# Sheet1.net
KiCad netlist of a schematic drawn in Altium Designer
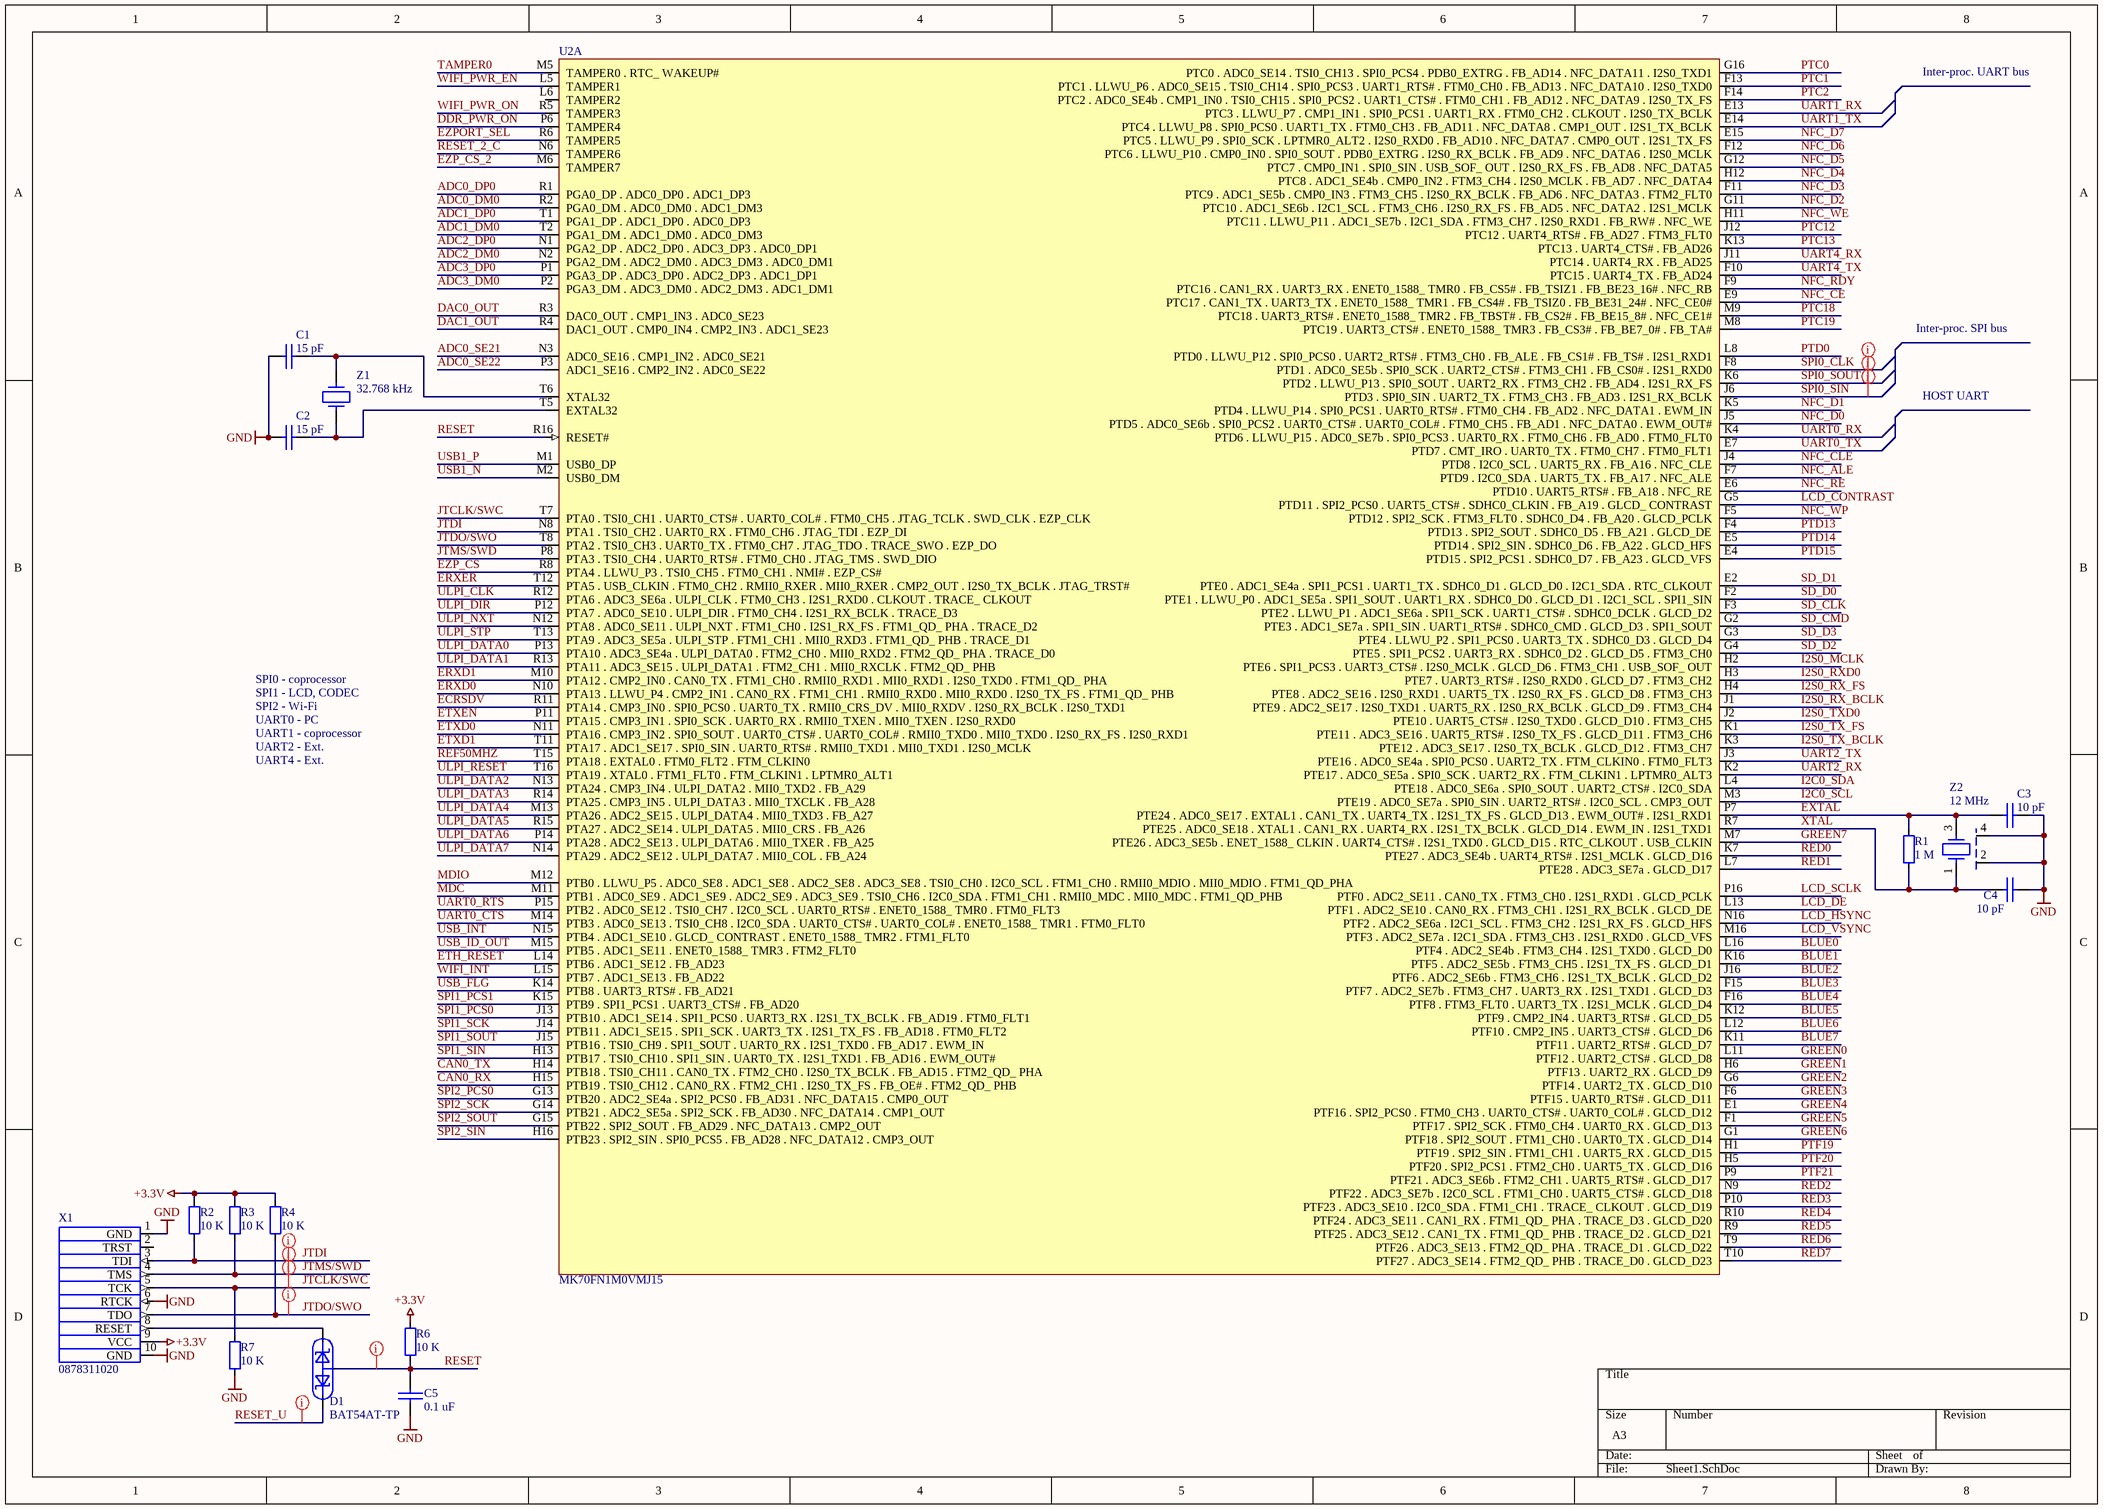
[diagram p0: Sheet1.SchDoc]

(export (version "E")
  (design (tool "Eeschema 10.0.6"))
  (components
    (comp (ref "C1")
      (value "15 pF")
      (footprint "1608[0603]")
      (description "15 pF, 50V, 5%, NP0, 0603 SMD MLC Capacitor")
      (fields (field (name "MANUFACTURER") "YAGEO AMERICA CORPORATION") (field (name "TOLERANCE") "5%"))
      (libsource (lib "ea_Capacitors") (part "CCPF015K0603"))
    )
    (comp (ref "C2")
      (value "15 pF")
      (footprint "1608[0603]")
      (description "15 pF, 50V, 5%, NP0, 0603 SMD MLC Capacitor")
      (fields (field (name "MANUFACTURER") "YAGEO AMERICA CORPORATION") (field (name "TOLERANCE") "5%"))
      (libsource (lib "ea_Capacitors") (part "CCPF015K0603"))
    )
    (comp (ref "C3")
      (value "10 pF")
      (footprint "1608[0603]")
      (description "10 pF, 50V, 5%, NP0, 0603 SMD MLC Capacitor")
      (fields (field (name "MANUFACTURER") "Kemet") (field (name "TOLERANCE") "5%"))
      (libsource (lib "ea_Capacitors") (part "CCPF010K0603"))
    )
    (comp (ref "C4")
      (value "10 pF")
      (footprint "1608[0603]")
      (description "10 pF, 50V, 5%, NP0, 0603 SMD MLC Capacitor")
      (fields (field (name "MANUFACTURER") "Kemet") (field (name "TOLERANCE") "5%"))
      (libsource (lib "ea_Capacitors") (part "CCPF010K0603"))
    )
    (comp (ref "C5")
      (value "0.1 uF")
      (footprint "1005[0402]")
      (description "0.1 uF, 16V, 10%, X7R, 0402")
      (fields (field (name "TOLERANCE") "10%") (field (name "MANUFACTURER") "Murata"))
      (libsource (lib "ea_Capacitors") (part "GRM155R71C104KA88D"))
    )
    (comp (ref "D1")
      (value "BAT54AT-TP")
      (footprint "SOT-523F")
      (description "Schottky Diode, 30 V, 200 mA, common anode, SOT523")
      (fields (field (name "MANUFACTURER") "Micro Commercial Co") (field (name "PARTNUM") "BAT54AT-TPDKR-ND"))
      (libsource (lib "ea_Diodes") (part "BAT54AT-TP"))
    )
    (comp (ref "R1")
      (value "1 M")
      (footprint "0603")
      (description "1 M, 1%, 0603, SMD Resistor, Taped")
      (fields (field (name "MANUFACTURER") "YAGEO AMERICA CORPORATION") (field (name "TOLERANCE") "1%"))
      (libsource (lib "ea_Resistors") (part "RC0603FR-071ML"))
    )
    (comp (ref "R2")
      (value "10 K")
      (footprint "0402")
      (description "10 K, 5%, 0402, SMD Resistor, Taped")
      (fields (field (name "MANUFACTURER") "Yageo") (field (name "TOLERANCE") "5%"))
      (libsource (lib "ea_Resistors") (part "RC0402JR-0710KL"))
    )
    (comp (ref "R3")
      (value "10 K")
      (footprint "0402")
      (description "10 K, 5%, 0402, SMD Resistor, Taped")
      (fields (field (name "MANUFACTURER") "Yageo") (field (name "TOLERANCE") "5%"))
      (libsource (lib "ea_Resistors") (part "RC0402JR-0710KL"))
    )
    (comp (ref "R4")
      (value "10 K")
      (footprint "0402")
      (description "10 K, 5%, 0402, SMD Resistor, Taped")
      (fields (field (name "MANUFACTURER") "Yageo") (field (name "TOLERANCE") "5%"))
      (libsource (lib "ea_Resistors") (part "RC0402JR-0710KL"))
    )
    (comp (ref "R6")
      (value "10 K")
      (footprint "0402")
      (description "10 K, 5%, 0402, SMD Resistor, Taped")
      (fields (field (name "MANUFACTURER") "Yageo") (field (name "TOLERANCE") "5%"))
      (libsource (lib "ea_Resistors") (part "RC0402JR-0710KL"))
    )
    (comp (ref "R7")
      (value "10 K")
      (footprint "0402")
      (description "10 K, 5%, 0402, SMD Resistor, Taped")
      (fields (field (name "MANUFACTURER") "Yageo") (field (name "TOLERANCE") "5%"))
      (libsource (lib "ea_Resistors") (part "RC0402JR-0710KL"))
    )
    (comp (ref "U2")
      (value "MK70FN1M0VMJ15")
      (footprint "MAPBGA 256-pin")
      (description "32-Bit 150 Mhz ARM 1MB FLASH 256MAPBGA")
      (fields (field (name "MANUFACTURER") "Freescale") (field (name "PARTNUM") "MK70FN1M0VMJ15-ND"))
      (libsource (lib "ea_IC_CPU") (part "MK70FN1M0VMJ15"))
    )
    (comp (ref "X1")
      (value "0878311020")
      (footprint "878311020 MGRID WALL HDR SMD")
      (description "JTAG, CONN HEADER 10POS 2MM VERT SMD")
      (fields (field (name "MANUFACTURER") "Molex Inc") (field (name "PARTNUM") "WM18639-ND"))
      (libsource (lib "ea_Connectors") (part "0878321020"))
    )
    (comp (ref "Z1")
      (value "32.768 kHz")
      (footprint "ABS10")
      (description "32.768 kHz, 12.5 pF, 70 kOhm, ±20ppm, -40°C ~ 80°C")
      (fields (field (name "MANUFACTURER") "Abracon Corporation") (field (name "PARTNUM") "535-9536-1-ND"))
      (libsource (lib "ea_OSC_CLK_GEN") (part "ABS10-32.768KHZ-T"))
    )
    (comp (ref "Z2")
      (value "12 MHz")
      (footprint "DSX321G")
      (description "12 MHz, 8 pF, ±15ppm, -10...+75 С")
      (fields (field (name "MANUFACTURER") "NDK") (field (name "PARTNUM") "644-1047-1-ND"))
      (libsource (lib "ea_OSC_CLK_GEN") (part "NX3225SA-12.000MHZ-STD-CSR-1"))
    )
  )
  (nets
    (net (code "1") (name "+3.3V") (class "Default")
      (node (ref "R2") (pin "1") (pinfunction "1_1") (pintype "passive"))
      (node (ref "R3") (pin "1") (pinfunction "1_1") (pintype "passive"))
      (node (ref "R4") (pin "1") (pinfunction "1_1") (pintype "passive"))
      (node (ref "R6") (pin "1") (pinfunction "1_1") (pintype "passive"))
      (node (ref "X1") (pin "9") (pinfunction "VCC_9") (pintype "power_in"))
    )
    (net (code "2") (name "/ADC0_DM0") (class "Default")
      (node (ref "U2") (pin "R2") (pinfunction "PGA0_DM_._ADC0_DM0_._ADC1_DM3_R2") (pintype "bidirectional"))
    )
    (net (code "3") (name "/ADC0_DP0") (class "Default")
      (node (ref "U2") (pin "R1") (pinfunction "PGA0_DP_._ADC0_DP0_._ADC1_DP3_R1") (pintype "bidirectional"))
    )
    (net (code "4") (name "/ADC0_SE21") (class "Default")
      (node (ref "U2") (pin "N3") (pinfunction "ADC0_SE16_._CMP1_IN2_._ADC0_SE21_N3") (pintype "bidirectional"))
    )
    (net (code "5") (name "/ADC0_SE22") (class "Default")
      (node (ref "U2") (pin "P3") (pinfunction "ADC1_SE16_._CMP2_IN2_._ADC0_SE22_P3") (pintype "bidirectional"))
    )
    (net (code "6") (name "/ADC1_DM0") (class "Default")
      (node (ref "U2") (pin "T2") (pinfunction "PGA1_DM_._ADC1_DM0_._ADC0_DM3_T2") (pintype "bidirectional"))
    )
    (net (code "7") (name "/ADC1_DP0") (class "Default")
      (node (ref "U2") (pin "T1") (pinfunction "PGA1_DP_._ADC1_DP0_._ADC0_DP3_T1") (pintype "bidirectional"))
    )
    (net (code "8") (name "/ADC2_DM0") (class "Default")
      (node (ref "U2") (pin "N2") (pinfunction "PGA2_DM_._ADC2_DM0_._ADC3_DM3_._ADC0_DM1_N2") (pintype "bidirectional"))
    )
    (net (code "9") (name "/ADC2_DP0") (class "Default")
      (node (ref "U2") (pin "N1") (pinfunction "PGA2_DP_._ADC2_DP0_._ADC3_DP3_._ADC0_DP1_N1") (pintype "bidirectional"))
    )
    (net (code "10") (name "/ADC3_DM0") (class "Default")
      (node (ref "U2") (pin "P2") (pinfunction "PGA3_DM_._ADC3_DM0_._ADC2_DM3_._ADC1_DM1_P2") (pintype "bidirectional"))
    )
    (net (code "11") (name "/ADC3_DP0") (class "Default")
      (node (ref "U2") (pin "P1") (pinfunction "PGA3_DP_._ADC3_DP0_._ADC2_DP3_._ADC1_DP1_P1") (pintype "bidirectional"))
    )
    (net (code "12") (name "/BLUE0") (class "Default")
      (node (ref "U2") (pin "L16") (pinfunction "PTF4_._ADC2_SE4b_._FTM3_CH4_._I2S1_TXD0_._GLCD_D0_L16") (pintype "bidirectional"))
    )
    (net (code "13") (name "/BLUE1") (class "Default")
      (node (ref "U2") (pin "K16") (pinfunction "PTF5_._ADC2_SE5b_._FTM3_CH5_._I2S1_TX_FS_._GLCD_D1_K16") (pintype "bidirectional"))
    )
    (net (code "14") (name "/BLUE2") (class "Default")
      (node (ref "U2") (pin "J16") (pinfunction "PTF6_._ADC2_SE6b_._FTM3_CH6_._I2S1_TX_BCLK_._GLCD_D2_J16") (pintype "bidirectional"))
    )
    (net (code "15") (name "/BLUE3") (class "Default")
      (node (ref "U2") (pin "F15") (pinfunction "PTF7_._ADC2_SE7b_._FTM3_CH7_._UART3_RX_._I2S1_TXD1_._GLCD_D3_F15") (pintype "bidirectional"))
    )
    (net (code "16") (name "/BLUE4") (class "Default")
      (node (ref "U2") (pin "F16") (pinfunction "PTF8_._FTM3_FLT0_._UART3_TX_._I2S1_MCLK_._GLCD_D4_F16") (pintype "bidirectional"))
    )
    (net (code "17") (name "/BLUE5") (class "Default")
      (node (ref "U2") (pin "K12") (pinfunction "PTF9_._CMP2_IN4_._UART3_RTS#_._GLCD_D5_K12") (pintype "bidirectional"))
    )
    (net (code "18") (name "/BLUE6") (class "Default")
      (node (ref "U2") (pin "L12") (pinfunction "PTF10_._CMP2_IN5_._UART3_CTS#_._GLCD_D6_L12") (pintype "bidirectional"))
    )
    (net (code "19") (name "/BLUE7") (class "Default")
      (node (ref "U2") (pin "K11") (pinfunction "PTF11_._UART2_RTS#_._GLCD_D7_K11") (pintype "bidirectional"))
    )
    (net (code "20") (name "/CAN0_RX") (class "Default")
      (node (ref "U2") (pin "H15") (pinfunction "PTB19_._TSI0_CH12_._CAN0_RX_._FTM2_CH1_._I2S0_TX_FS_._FB_OE#_._FTM2_QD__PHB_H15") (pintype "bidirectional"))
    )
    (net (code "21") (name "/CAN0_TX") (class "Default")
      (node (ref "U2") (pin "H14") (pinfunction "PTB18_._TSI0_CH11_._CAN0_TX_._FTM2_CH0_._I2S0_TX_BCLK_._FB_AD15_._FTM2_QD__PHA_H14") (pintype "bidirectional"))
    )
    (net (code "22") (name "/DAC0_OUT") (class "Default")
      (node (ref "U2") (pin "R3") (pinfunction "DAC0_OUT_._CMP1_IN3_._ADC0_SE23_R3") (pintype "bidirectional"))
    )
    (net (code "23") (name "/DAC1_OUT") (class "Default")
      (node (ref "U2") (pin "R4") (pinfunction "DAC1_OUT_._CMP0_IN4_._CMP2_IN3_._ADC1_SE23_R4") (pintype "bidirectional"))
    )
    (net (code "24") (name "/DDR_PWR_ON") (class "Default")
      (node (ref "U2") (pin "P6") (pinfunction "TAMPER4_P6") (pintype "bidirectional"))
    )
    (net (code "25") (name "/ECRSDV") (class "Default")
      (node (ref "U2") (pin "R11") (pinfunction "PTA14_._CMP3_IN0_._SPI0_PCS0_._UART0_TX_._RMII0_CRS_DV_._MII0_RXDV_._I2S0_RX_BCLK_._I2S0_TXD1_R11") (pintype "bidirectional"))
    )
    (net (code "26") (name "/ERXD0") (class "Default")
      (node (ref "U2") (pin "N10") (pinfunction "PTA13_._LLWU_P4_._CMP2_IN1_._CAN0_RX_._FTM1_CH1_._RMII0_RXD0_._MII0_RXD0_._I2S0_TX_FS_._FTM1_QD__PHB_N10") (pintype "bidirectional"))
    )
    (net (code "27") (name "/ERXD1") (class "Default")
      (node (ref "U2") (pin "M10") (pinfunction "PTA12_._CMP2_IN0_._CAN0_TX_._FTM1_CH0_._RMII0_RXD1_._MII0_RXD1_._I2S0_TXD0_._FTM1_QD__PHA_M10") (pintype "bidirectional"))
    )
    (net (code "28") (name "/ERXER") (class "Default")
      (node (ref "U2") (pin "T12") (pinfunction "PTA5_._USB_CLKIN_._FTM0_CH2_._RMII0_RXER_._MII0_RXER_._CMP2_OUT_._I2S0_TX_BCLK_._JTAG_TRST#_T12") (pintype "bidirectional"))
    )
    (net (code "29") (name "/ETH_RESET") (class "Default")
      (node (ref "U2") (pin "L14") (pinfunction "PTB6_._ADC1_SE12_._FB_AD23_L14") (pintype "bidirectional"))
    )
    (net (code "30") (name "/ETXD0") (class "Default")
      (node (ref "U2") (pin "N11") (pinfunction "PTA16_._CMP3_IN2_._SPI0_SOUT_._UART0_CTS#_._UART0_COL#_._RMII0_TXD0_._MII0_TXD0_._I2S0_RX_FS_._I2S0_RXD1_N11") (pintype "bidirectional"))
    )
    (net (code "31") (name "/ETXD1") (class "Default")
      (node (ref "U2") (pin "T11") (pinfunction "PTA17_._ADC1_SE17_._SPI0_SIN_._UART0_RTS#_._RMII0_TXD1_._MII0_TXD1_._I2S0_MCLK_T11") (pintype "bidirectional"))
    )
    (net (code "32") (name "/ETXEN") (class "Default")
      (node (ref "U2") (pin "P11") (pinfunction "PTA15_._CMP3_IN1_._SPI0_SCK_._UART0_RX_._RMII0_TXEN_._MII0_TXEN_._I2S0_RXD0_P11") (pintype "bidirectional"))
    )
    (net (code "33") (name "/EXTAL") (class "Default")
      (node (ref "C3") (pin "1") (pinfunction "1_1") (pintype "passive"))
      (node (ref "R1") (pin "2") (pinfunction "2_2") (pintype "passive"))
      (node (ref "U2") (pin "P7") (pinfunction "PTE24_._ADC0_SE17_._EXTAL1_._CAN1_TX_._UART4_TX_._I2S1_TX_FS_._GLCD_D13_._EWM_OUT#_._I2S1_RXD1_P7") (pintype "bidirectional"))
      (node (ref "Z2") (pin "3") (pinfunction "3_3") (pintype "passive"))
    )
    (net (code "34") (name "/EZPORT_SEL") (class "Default")
      (node (ref "U2") (pin "R6") (pinfunction "TAMPER5_R6") (pintype "bidirectional"))
    )
    (net (code "35") (name "/EZP_CS") (class "Default")
      (node (ref "U2") (pin "R8") (pinfunction "PTA4_._LLWU_P3_._TSI0_CH5_._FTM0_CH1_._NMI#_._EZP_CS#_R8") (pintype "bidirectional"))
    )
    (net (code "36") (name "/EZP_CS_2") (class "Default")
      (node (ref "U2") (pin "M6") (pinfunction "TAMPER7_M6") (pintype "bidirectional"))
    )
    (net (code "37") (name "/GREEN0") (class "Default")
      (node (ref "U2") (pin "L11") (pinfunction "PTF12_._UART2_CTS#_._GLCD_D8_L11") (pintype "bidirectional"))
    )
    (net (code "38") (name "/GREEN1") (class "Default")
      (node (ref "U2") (pin "H6") (pinfunction "PTF13_._UART2_RX_._GLCD_D9_H6") (pintype "bidirectional"))
    )
    (net (code "39") (name "/GREEN2") (class "Default")
      (node (ref "U2") (pin "G6") (pinfunction "PTF14_._UART2_TX_._GLCD_D10_G6") (pintype "bidirectional"))
    )
    (net (code "40") (name "/GREEN3") (class "Default")
      (node (ref "U2") (pin "F6") (pinfunction "PTF15_._UART0_RTS#_._GLCD_D11_F6") (pintype "bidirectional"))
    )
    (net (code "41") (name "/GREEN4") (class "Default")
      (node (ref "U2") (pin "E1") (pinfunction "PTF16_._SPI2_PCS0_._FTM0_CH3_._UART0_CTS#_._UART0_COL#_._GLCD_D12_E1") (pintype "bidirectional"))
    )
    (net (code "42") (name "/GREEN5") (class "Default")
      (node (ref "U2") (pin "F1") (pinfunction "PTF17_._SPI2_SCK_._FTM0_CH4_._UART0_RX_._GLCD_D13_F1") (pintype "bidirectional"))
    )
    (net (code "43") (name "/GREEN6") (class "Default")
      (node (ref "U2") (pin "G1") (pinfunction "PTF18_._SPI2_SOUT_._FTM1_CH0_._UART0_TX_._GLCD_D14_G1") (pintype "bidirectional"))
    )
    (net (code "44") (name "/GREEN7") (class "Default")
      (node (ref "U2") (pin "M7") (pinfunction "PTE26_._ADC3_SE5b_._ENET_1588__CLKIN_._UART4_CTS#_._I2S1_TXD0_._GLCD_D15_._RTC_CLKOUT_._USB_CLKIN_M7") (pintype "bidirectional"))
    )
    (net (code "45") (name "/I2C0_SCL") (class "Default")
      (node (ref "U2") (pin "M3") (pinfunction "PTE19_._ADC0_SE7a_._SPI0_SIN_._UART2_RTS#_._I2C0_SCL_._CMP3_OUT_M3") (pintype "bidirectional"))
    )
    (net (code "46") (name "/I2C0_SDA") (class "Default")
      (node (ref "U2") (pin "L4") (pinfunction "PTE18_._ADC0_SE6a_._SPI0_SOUT_._UART2_CTS#_._I2C0_SDA_L4") (pintype "bidirectional"))
    )
    (net (code "47") (name "/I2S0_MCLK") (class "Default")
      (node (ref "U2") (pin "H2") (pinfunction "PTE6_._SPI1_PCS3_._UART3_CTS#_._I2S0_MCLK_._GLCD_D6_._FTM3_CH1_._USB_SOF__OUT_H2") (pintype "bidirectional"))
    )
    (net (code "48") (name "/I2S0_RXD0") (class "Default")
      (node (ref "U2") (pin "H3") (pinfunction "PTE7_._UART3_RTS#_._I2S0_RXD0_._GLCD_D7_._FTM3_CH2_H3") (pintype "bidirectional"))
    )
    (net (code "49") (name "/I2S0_RX_BCLK") (class "Default")
      (node (ref "U2") (pin "J1") (pinfunction "PTE9_._ADC2_SE17_._I2S0_TXD1_._UART5_RX_._I2S0_RX_BCLK_._GLCD_D9_._FTM3_CH4_J1") (pintype "bidirectional"))
    )
    (net (code "50") (name "/I2S0_RX_FS") (class "Default")
      (node (ref "U2") (pin "H4") (pinfunction "PTE8_._ADC2_SE16_._I2S0_RXD1_._UART5_TX_._I2S0_RX_FS_._GLCD_D8_._FTM3_CH3_H4") (pintype "bidirectional"))
    )
    (net (code "51") (name "/I2S0_TXD0") (class "Default")
      (node (ref "U2") (pin "J2") (pinfunction "PTE10_._UART5_CTS#_._I2S0_TXD0_._GLCD_D10_._FTM3_CH5_J2") (pintype "bidirectional"))
    )
    (net (code "52") (name "/I2S0_TX_BCLK") (class "Default")
      (node (ref "U2") (pin "K3") (pinfunction "PTE12_._ADC3_SE17_._I2S0_TX_BCLK_._GLCD_D12_._FTM3_CH7_K3") (pintype "bidirectional"))
    )
    (net (code "53") (name "/I2S0_TX_FS") (class "Default")
      (node (ref "U2") (pin "K1") (pinfunction "PTE11_._ADC3_SE16_._UART5_RTS#_._I2S0_TX_FS_._GLCD_D11_._FTM3_CH6_K1") (pintype "bidirectional"))
    )
    (net (code "54") (name "/JTCLK{slash}SWC") (class "Default")
      (node (ref "R7") (pin "1") (pinfunction "1_1") (pintype "passive"))
      (node (ref "U2") (pin "T7") (pinfunction "PTA0_._TSI0_CH1_._UART0_CTS#_._UART0_COL#_._FTM0_CH5_._JTAG_TCLK_._SWD_CLK_._EZP_CLK_T7") (pintype "bidirectional"))
      (node (ref "X1") (pin "5") (pinfunction "TCK_5") (pintype "output"))
    )
    (net (code "55") (name "/JTDI") (class "Default")
      (node (ref "R2") (pin "2") (pinfunction "2_2") (pintype "passive"))
      (node (ref "U2") (pin "N8") (pinfunction "PTA1_._TSI0_CH2_._UART0_RX_._FTM0_CH6_._JTAG_TDI_._EZP_DI_N8") (pintype "bidirectional"))
      (node (ref "X1") (pin "3") (pinfunction "TDI_3") (pintype "input"))
    )
    (net (code "56") (name "/JTDO{slash}SWO") (class "Default")
      (node (ref "R4") (pin "2") (pinfunction "2_2") (pintype "passive"))
      (node (ref "U2") (pin "T8") (pinfunction "PTA2_._TSI0_CH3_._UART0_TX_._FTM0_CH7_._JTAG_TDO_._TRACE_SWO_._EZP_DO_T8") (pintype "bidirectional"))
      (node (ref "X1") (pin "7") (pinfunction "TDO_7") (pintype "output"))
    )
    (net (code "57") (name "/JTMS{slash}SWD") (class "Default")
      (node (ref "R3") (pin "2") (pinfunction "2_2") (pintype "passive"))
      (node (ref "U2") (pin "P8") (pinfunction "PTA3_._TSI0_CH4_._UART0_RTS#_._FTM0_CH0_._JTAG_TMS_._SWD_DIO_P8") (pintype "bidirectional"))
      (node (ref "X1") (pin "4") (pinfunction "TMS_4") (pintype "output"))
    )
    (net (code "58") (name "/LCD_CONTRAST") (class "Default")
      (node (ref "U2") (pin "G5") (pinfunction "PTD11_._SPI2_PCS0_._UART5_CTS#_._SDHC0_CLKIN_._FB_A19_._GLCD__CONTRAST_G5") (pintype "bidirectional"))
    )
    (net (code "59") (name "/LCD_DE") (class "Default")
      (node (ref "U2") (pin "L13") (pinfunction "PTF1_._ADC2_SE10_._CAN0_RX_._FTM3_CH1_._I2S1_RX_BCLK_._GLCD_DE_L13") (pintype "bidirectional"))
    )
    (net (code "60") (name "/LCD_HSYNC") (class "Default")
      (node (ref "U2") (pin "N16") (pinfunction "PTF2_._ADC2_SE6a_._I2C1_SCL_._FTM3_CH2_._I2S1_RX_FS_._GLCD_HFS_N16") (pintype "bidirectional"))
    )
    (net (code "61") (name "/LCD_SCLK") (class "Default")
      (node (ref "U2") (pin "P16") (pinfunction "PTF0_._ADC2_SE11_._CAN0_TX_._FTM3_CH0_._I2S1_RXD1_._GLCD_PCLK_P16") (pintype "bidirectional"))
    )
    (net (code "62") (name "/LCD_VSYNC") (class "Default")
      (node (ref "U2") (pin "M16") (pinfunction "PTF3_._ADC2_SE7a_._I2C1_SDA_._FTM3_CH3_._I2S1_RXD0_._GLCD_VFS_M16") (pintype "bidirectional"))
    )
    (net (code "63") (name "/MDC") (class "Default")
      (node (ref "U2") (pin "M11") (pinfunction "PTB1_._ADC0_SE9_._ADC1_SE9_._ADC2_SE9_._ADC3_SE9_._TSI0_CH6_._I2C0_SDA_._FTM1_CH1_._RMII0_MDC_._MII0_MDC_._FTM1_QD_PHB_M11") (pintype "bidirectional"))
    )
    (net (code "64") (name "/MDIO") (class "Default")
      (node (ref "U2") (pin "M12") (pinfunction "PTB0_._LLWU_P5_._ADC0_SE8_._ADC1_SE8_._ADC2_SE8_._ADC3_SE8_._TSI0_CH0_._I2C0_SCL_._FTM1_CH0_._RMII0_MDIO_._MII0_MDIO_._FTM1_QD_PHA_M12") (pintype "bidirectional"))
    )
    (net (code "65") (name "/NFC_ALE") (class "Default")
      (node (ref "U2") (pin "F7") (pinfunction "PTD9_._I2C0_SDA_._UART5_TX_._FB_A17_._NFC_ALE_F7") (pintype "bidirectional"))
    )
    (net (code "66") (name "/NFC_CE") (class "Default")
      (node (ref "U2") (pin "E9") (pinfunction "PTC17_._CAN1_TX_._UART3_TX_._ENET0_1588__TMR1_._FB_CS4#_._FB_TSIZ0_._FB_BE31_24#_._NFC_CE0#_E9") (pintype "bidirectional"))
    )
    (net (code "67") (name "/NFC_CLE") (class "Default")
      (node (ref "U2") (pin "J4") (pinfunction "PTD8_._I2C0_SCL_._UART5_RX_._FB_A16_._NFC_CLE_J4") (pintype "bidirectional"))
    )
    (net (code "68") (name "/NFC_D0") (class "Default")
      (node (ref "U2") (pin "J5") (pinfunction "PTD5_._ADC0_SE6b_._SPI0_PCS2_._UART0_CTS#_._UART0_COL#_._FTM0_CH5_._FB_AD1_._NFC_DATA0_._EWM_OUT#_J5") (pintype "bidirectional"))
    )
    (net (code "69") (name "/NFC_D1") (class "Default")
      (node (ref "U2") (pin "K5") (pinfunction "PTD4_._LLWU_P14_._SPI0_PCS1_._UART0_RTS#_._FTM0_CH4_._FB_AD2_._NFC_DATA1_._EWM_IN_K5") (pintype "bidirectional"))
    )
    (net (code "70") (name "/NFC_D2") (class "Default")
      (node (ref "U2") (pin "G11") (pinfunction "PTC10_._ADC1_SE6b_._I2C1_SCL_._FTM3_CH6_._I2S0_RX_FS_._FB_AD5_._NFC_DATA2_._I2S1_MCLK_G11") (pintype "bidirectional"))
    )
    (net (code "71") (name "/NFC_D3") (class "Default")
      (node (ref "U2") (pin "F11") (pinfunction "PTC9_._ADC1_SE5b_._CMP0_IN3_._FTM3_CH5_._I2S0_RX_BCLK_._FB_AD6_._NFC_DATA3_._FTM2_FLT0_F11") (pintype "bidirectional"))
    )
    (net (code "72") (name "/NFC_D4") (class "Default")
      (node (ref "U2") (pin "H12") (pinfunction "PTC8_._ADC1_SE4b_._CMP0_IN2_._FTM3_CH4_._I2S0_MCLK_._FB_AD7_._NFC_DATA4_H12") (pintype "bidirectional"))
    )
    (net (code "73") (name "/NFC_D5") (class "Default")
      (node (ref "U2") (pin "G12") (pinfunction "PTC7_._CMP0_IN1_._SPI0_SIN_._USB_SOF__OUT_._I2S0_RX_FS_._FB_AD8_._NFC_DATA5_G12") (pintype "bidirectional"))
    )
    (net (code "74") (name "/NFC_D6") (class "Default")
      (node (ref "U2") (pin "F12") (pinfunction "PTC6_._LLWU_P10_._CMP0_IN0_._SPI0_SOUT_._PDB0_EXTRG_._I2S0_RX_BCLK_._FB_AD9_._NFC_DATA6_._I2S0_MCLK_F12") (pintype "bidirectional"))
    )
    (net (code "75") (name "/NFC_D7") (class "Default")
      (node (ref "U2") (pin "E15") (pinfunction "PTC5_._LLWU_P9_._SPI0_SCK_._LPTMR0_ALT2_._I2S0_RXD0_._FB_AD10_._NFC_DATA7_._CMP0_OUT_._I2S1_TX_FS_E15") (pintype "bidirectional"))
    )
    (net (code "76") (name "/NFC_RDY") (class "Default")
      (node (ref "U2") (pin "F9") (pinfunction "PTC16_._CAN1_RX_._UART3_RX_._ENET0_1588__TMR0_._FB_CS5#_._FB_TSIZ1_._FB_BE23_16#_._NFC_RB_F9") (pintype "bidirectional"))
    )
    (net (code "77") (name "/NFC_RE") (class "Default")
      (node (ref "U2") (pin "E6") (pinfunction "PTD10_._UART5_RTS#_._FB_A18_._NFC_RE_E6") (pintype "bidirectional"))
    )
    (net (code "78") (name "/NFC_WE") (class "Default")
      (node (ref "U2") (pin "H11") (pinfunction "PTC11_._LLWU_P11_._ADC1_SE7b_._I2C1_SDA_._FTM3_CH7_._I2S0_RXD1_._FB_RW#_._NFC_WE_H11") (pintype "bidirectional"))
    )
    (net (code "79") (name "/NFC_WP") (class "Default")
      (node (ref "U2") (pin "F5") (pinfunction "PTD12_._SPI2_SCK_._FTM3_FLT0_._SDHC0_D4_._FB_A20_._GLCD_PCLK_F5") (pintype "bidirectional"))
    )
    (net (code "80") (name "/PTC0") (class "Default")
      (node (ref "U2") (pin "G16") (pinfunction "PTC0_._ADC0_SE14_._TSI0_CH13_._SPI0_PCS4_._PDB0_EXTRG_._FB_AD14_._NFC_DATA11_._I2S0_TXD1_G16") (pintype "bidirectional"))
    )
    (net (code "81") (name "/PTC1") (class "Default")
      (node (ref "U2") (pin "F13") (pinfunction "PTC1_._LLWU_P6_._ADC0_SE15_._TSI0_CH14_._SPI0_PCS3_._UART1_RTS#_._FTM0_CH0_._FB_AD13_._NFC_DATA10_._I2S0_TXD0_F13") (pintype "bidirectional"))
    )
    (net (code "82") (name "/PTC2") (class "Default")
      (node (ref "U2") (pin "F14") (pinfunction "PTC2_._ADC0_SE4b_._CMP1_IN0_._TSI0_CH15_._SPI0_PCS2_._UART1_CTS#_._FTM0_CH1_._FB_AD12_._NFC_DATA9_._I2S0_TX_FS_F14") (pintype "bidirectional"))
    )
    (net (code "83") (name "/PTC12") (class "Default")
      (node (ref "U2") (pin "J12") (pinfunction "PTC12_._UART4_RTS#_._FB_AD27_._FTM3_FLT0_J12") (pintype "bidirectional"))
    )
    (net (code "84") (name "/PTC13") (class "Default")
      (node (ref "U2") (pin "K13") (pinfunction "PTC13_._UART4_CTS#_._FB_AD26_K13") (pintype "bidirectional"))
    )
    (net (code "85") (name "/PTC18") (class "Default")
      (node (ref "U2") (pin "M9") (pinfunction "PTC18_._UART3_RTS#_._ENET0_1588__TMR2_._FB_TBST#_._FB_CS2#_._FB_BE15_8#_._NFC_CE1#_M9") (pintype "bidirectional"))
    )
    (net (code "86") (name "/PTC19") (class "Default")
      (node (ref "U2") (pin "M8") (pinfunction "PTC19_._UART3_CTS#_._ENET0_1588__TMR3_._FB_CS3#_._FB_BE7_0#_._FB_TA#_M8") (pintype "bidirectional"))
    )
    (net (code "87") (name "/PTD0") (class "Default")
      (node (ref "U2") (pin "L8") (pinfunction "PTD0_._LLWU_P12_._SPI0_PCS0_._UART2_RTS#_._FTM3_CH0_._FB_ALE_._FB_CS1#_._FB_TS#_._I2S1_RXD1_L8") (pintype "bidirectional"))
    )
    (net (code "88") (name "/PTD13") (class "Default")
      (node (ref "U2") (pin "F4") (pinfunction "PTD13_._SPI2_SOUT_._SDHC0_D5_._FB_A21_._GLCD_DE_F4") (pintype "bidirectional"))
    )
    (net (code "89") (name "/PTD14") (class "Default")
      (node (ref "U2") (pin "E5") (pinfunction "PTD14_._SPI2_SIN_._SDHC0_D6_._FB_A22_._GLCD_HFS_E5") (pintype "bidirectional"))
    )
    (net (code "90") (name "/PTD15") (class "Default")
      (node (ref "U2") (pin "E4") (pinfunction "PTD15_._SPI2_PCS1_._SDHC0_D7_._FB_A23_._GLCD_VFS_E4") (pintype "bidirectional"))
    )
    (net (code "91") (name "/PTF19") (class "Default")
      (node (ref "U2") (pin "H1") (pinfunction "PTF19_._SPI2_SIN_._FTM1_CH1_._UART5_RX_._GLCD_D15_H1") (pintype "bidirectional"))
    )
    (net (code "92") (name "/PTF20") (class "Default")
      (node (ref "U2") (pin "H5") (pinfunction "PTF20_._SPI2_PCS1_._FTM2_CH0_._UART5_TX_._GLCD_D16_H5") (pintype "bidirectional"))
    )
    (net (code "93") (name "/PTF21") (class "Default")
      (node (ref "U2") (pin "P9") (pinfunction "PTF21_._ADC3_SE6b_._FTM2_CH1_._UART5_RTS#_._GLCD_D17_P9") (pintype "bidirectional"))
    )
    (net (code "94") (name "/RED0") (class "Default")
      (node (ref "U2") (pin "K7") (pinfunction "PTE27_._ADC3_SE4b_._UART4_RTS#_._I2S1_MCLK_._GLCD_D16_K7") (pintype "bidirectional"))
    )
    (net (code "95") (name "/RED1") (class "Default")
      (node (ref "U2") (pin "L7") (pinfunction "PTE28_._ADC3_SE7a_._GLCD_D17_L7") (pintype "bidirectional"))
    )
    (net (code "96") (name "/RED2") (class "Default")
      (node (ref "U2") (pin "N9") (pinfunction "PTF22_._ADC3_SE7b_._I2C0_SCL_._FTM1_CH0_._UART5_CTS#_._GLCD_D18_N9") (pintype "bidirectional"))
    )
    (net (code "97") (name "/RED3") (class "Default")
      (node (ref "U2") (pin "P10") (pinfunction "PTF23_._ADC3_SE10_._I2C0_SDA_._FTM1_CH1_._TRACE__CLKOUT_._GLCD_D19_P10") (pintype "bidirectional"))
    )
    (net (code "98") (name "/RED4") (class "Default")
      (node (ref "U2") (pin "R10") (pinfunction "PTF24_._ADC3_SE11_._CAN1_RX_._FTM1_QD__PHA_._TRACE_D3_._GLCD_D20_R10") (pintype "bidirectional"))
    )
    (net (code "99") (name "/RED5") (class "Default")
      (node (ref "U2") (pin "R9") (pinfunction "PTF25_._ADC3_SE12_._CAN1_TX_._FTM1_QD__PHB_._TRACE_D2_._GLCD_D21_R9") (pintype "bidirectional"))
    )
    (net (code "100") (name "/RED6") (class "Default")
      (node (ref "U2") (pin "T9") (pinfunction "PTF26_._ADC3_SE13_._FTM2_QD__PHA_._TRACE_D1_._GLCD_D22_T9") (pintype "bidirectional"))
    )
    (net (code "101") (name "/RED7") (class "Default")
      (node (ref "U2") (pin "T10") (pinfunction "PTF27_._ADC3_SE14_._FTM2_QD__PHB_._TRACE_D0_._GLCD_D23_T10") (pintype "bidirectional"))
    )
    (net (code "102") (name "/REF50MHZ") (class "Default")
      (node (ref "U2") (pin "T15") (pinfunction "PTA18_._EXTAL0_._FTM0_FLT2_._FTM_CLKIN0_T15") (pintype "bidirectional"))
    )
    (net (code "103") (name "/RESET") (class "Default")
      (node (ref "C5") (pin "1") (pinfunction "1_1") (pintype "passive"))
      (node (ref "D1") (pin "3") (pintype "passive"))
      (node (ref "R6") (pin "2") (pinfunction "2_2") (pintype "passive"))
      (node (ref "U2") (pin "R16") (pinfunction "RESET#_R16") (pintype "input"))
    )
    (net (code "104") (name "/RESET_2_C") (class "Default")
      (node (ref "U2") (pin "N6") (pinfunction "TAMPER6_N6") (pintype "bidirectional"))
    )
    (net (code "105") (name "/RESET_U") (class "Default") (node (ref "D1") (pin "2") (pintype "passive")))
    (net (code "106") (name "/SD_CLK") (class "Default")
      (node (ref "U2") (pin "F3") (pinfunction "PTE2_._LLWU_P1_._ADC1_SE6a_._SPI1_SCK_._UART1_CTS#_._SDHC0_DCLK_._GLCD_D2_F3") (pintype "bidirectional"))
    )
    (net (code "107") (name "/SD_CMD") (class "Default")
      (node (ref "U2") (pin "G2") (pinfunction "PTE3_._ADC1_SE7a_._SPI1_SIN_._UART1_RTS#_._SDHC0_CMD_._GLCD_D3_._SPI1_SOUT_G2") (pintype "bidirectional"))
    )
    (net (code "108") (name "/SD_D0") (class "Default")
      (node (ref "U2") (pin "F2") (pinfunction "PTE1_._LLWU_P0_._ADC1_SE5a_._SPI1_SOUT_._UART1_RX_._SDHC0_D0_._GLCD_D1_._I2C1_SCL_._SPI1_SIN_F2") (pintype "bidirectional"))
    )
    (net (code "109") (name "/SD_D1") (class "Default")
      (node (ref "U2") (pin "E2") (pinfunction "PTE0_._ADC1_SE4a_._SPI1_PCS1_._UART1_TX_._SDHC0_D1_._GLCD_D0_._I2C1_SDA_._RTC_CLKOUT_E2") (pintype "bidirectional"))
    )
    (net (code "110") (name "/SD_D2") (class "Default")
      (node (ref "U2") (pin "G4") (pinfunction "PTE5_._SPI1_PCS2_._UART3_RX_._SDHC0_D2_._GLCD_D5_._FTM3_CH0_G4") (pintype "bidirectional"))
    )
    (net (code "111") (name "/SD_D3") (class "Default")
      (node (ref "U2") (pin "G3") (pinfunction "PTE4_._LLWU_P2_._SPI1_PCS0_._UART3_TX_._SDHC0_D3_._GLCD_D4_G3") (pintype "bidirectional"))
    )
    (net (code "112") (name "/SPI0_CLK") (class "Default")
      (node (ref "U2") (pin "F8") (pinfunction "PTD1_._ADC0_SE5b_._SPI0_SCK_._UART2_CTS#_._FTM3_CH1_._FB_CS0#_._I2S1_RXD0_F8") (pintype "bidirectional"))
    )
    (net (code "113") (name "/SPI0_SIN") (class "Default")
      (node (ref "U2") (pin "J6") (pinfunction "PTD3_._SPI0_SIN_._UART2_TX_._FTM3_CH3_._FB_AD3_._I2S1_RX_BCLK_J6") (pintype "bidirectional"))
    )
    (net (code "114") (name "/SPI0_SOUT") (class "Default")
      (node (ref "U2") (pin "K6") (pinfunction "PTD2_._LLWU_P13_._SPI0_SOUT_._UART2_RX_._FTM3_CH2_._FB_AD4_._I2S1_RX_FS_K6") (pintype "bidirectional"))
    )
    (net (code "115") (name "/SPI1_PCS0") (class "Default")
      (node (ref "U2") (pin "J13") (pinfunction "PTB10_._ADC1_SE14_._SPI1_PCS0_._UART3_RX_._I2S1_TX_BCLK_._FB_AD19_._FTM0_FLT1_J13") (pintype "bidirectional"))
    )
    (net (code "116") (name "/SPI1_PCS1") (class "Default")
      (node (ref "U2") (pin "K15") (pinfunction "PTB9_._SPI1_PCS1_._UART3_CTS#_._FB_AD20_K15") (pintype "bidirectional"))
    )
    (net (code "117") (name "/SPI1_SCK") (class "Default")
      (node (ref "U2") (pin "J14") (pinfunction "PTB11_._ADC1_SE15_._SPI1_SCK_._UART3_TX_._I2S1_TX_FS_._FB_AD18_._FTM0_FLT2_J14") (pintype "bidirectional"))
    )
    (net (code "118") (name "/SPI1_SIN") (class "Default")
      (node (ref "U2") (pin "H13") (pinfunction "PTB17_._TSI0_CH10_._SPI1_SIN_._UART0_TX_._I2S1_TXD1_._FB_AD16_._EWM_OUT#_H13") (pintype "bidirectional"))
    )
    (net (code "119") (name "/SPI1_SOUT") (class "Default")
      (node (ref "U2") (pin "J15") (pinfunction "PTB16_._TSI0_CH9_._SPI1_SOUT_._UART0_RX_._I2S1_TXD0_._FB_AD17_._EWM_IN_J15") (pintype "bidirectional"))
    )
    (net (code "120") (name "/SPI2_PCS0") (class "Default")
      (node (ref "U2") (pin "G13") (pinfunction "PTB20_._ADC2_SE4a_._SPI2_PCS0_._FB_AD31_._NFC_DATA15_._CMP0_OUT_G13") (pintype "bidirectional"))
    )
    (net (code "121") (name "/SPI2_SCK") (class "Default")
      (node (ref "U2") (pin "G14") (pinfunction "PTB21_._ADC2_SE5a_._SPI2_SCK_._FB_AD30_._NFC_DATA14_._CMP1_OUT_G14") (pintype "bidirectional"))
    )
    (net (code "122") (name "/SPI2_SIN") (class "Default")
      (node (ref "U2") (pin "H16") (pinfunction "PTB23_._SPI2_SIN_._SPI0_PCS5_._FB_AD28_._NFC_DATA12_._CMP3_OUT_H16") (pintype "bidirectional"))
    )
    (net (code "123") (name "/SPI2_SOUT") (class "Default")
      (node (ref "U2") (pin "G15") (pinfunction "PTB22_._SPI2_SOUT_._FB_AD29_._NFC_DATA13_._CMP2_OUT_G15") (pintype "bidirectional"))
    )
    (net (code "124") (name "/TAMPER0") (class "Default")
      (node (ref "U2") (pin "M5") (pinfunction "TAMPER0_._RTC__WAKEUP#_M5") (pintype "bidirectional"))
    )
    (net (code "125") (name "/UART0_CTS") (class "Default")
      (node (ref "U2") (pin "M14") (pinfunction "PTB3_._ADC0_SE13_._TSI0_CH8_._I2C0_SDA_._UART0_CTS#_._UART0_COL#_._ENET0_1588__TMR1_._FTM0_FLT0_M14") (pintype "bidirectional"))
    )
    (net (code "126") (name "/UART0_RTS") (class "Default")
      (node (ref "U2") (pin "P15") (pinfunction "PTB2_._ADC0_SE12_._TSI0_CH7_._I2C0_SCL_._UART0_RTS#_._ENET0_1588__TMR0_._FTM0_FLT3_P15") (pintype "bidirectional"))
    )
    (net (code "127") (name "/UART0_RX") (class "Default")
      (node (ref "U2") (pin "K4") (pinfunction "PTD6_._LLWU_P15_._ADC0_SE7b_._SPI0_PCS3_._UART0_RX_._FTM0_CH6_._FB_AD0_._FTM0_FLT0_K4") (pintype "bidirectional"))
    )
    (net (code "128") (name "/UART0_TX") (class "Default")
      (node (ref "U2") (pin "E7") (pinfunction "PTD7_._CMT_IRO_._UART0_TX_._FTM0_CH7_._FTM0_FLT1_E7") (pintype "bidirectional"))
    )
    (net (code "129") (name "/UART1_RX") (class "Default")
      (node (ref "U2") (pin "E13") (pinfunction "PTC3_._LLWU_P7_._CMP1_IN1_._SPI0_PCS1_._UART1_RX_._FTM0_CH2_._CLKOUT_._I2S0_TX_BCLK_E13") (pintype "bidirectional"))
    )
    (net (code "130") (name "/UART1_TX") (class "Default")
      (node (ref "U2") (pin "E14") (pinfunction "PTC4_._LLWU_P8_._SPI0_PCS0_._UART1_TX_._FTM0_CH3_._FB_AD11_._NFC_DATA8_._CMP1_OUT_._I2S1_TX_BCLK_E14") (pintype "bidirectional"))
    )
    (net (code "131") (name "/UART2_RX") (class "Default")
      (node (ref "U2") (pin "K2") (pinfunction "PTE17_._ADC0_SE5a_._SPI0_SCK_._UART2_RX_._FTM_CLKIN1_._LPTMR0_ALT3_K2") (pintype "bidirectional"))
    )
    (net (code "132") (name "/UART2_TX") (class "Default")
      (node (ref "U2") (pin "J3") (pinfunction "PTE16_._ADC0_SE4a_._SPI0_PCS0_._UART2_TX_._FTM_CLKIN0_._FTM0_FLT3_J3") (pintype "bidirectional"))
    )
    (net (code "133") (name "/UART4_RX") (class "Default")
      (node (ref "U2") (pin "J11") (pinfunction "PTC14_._UART4_RX_._FB_AD25_J11") (pintype "bidirectional"))
    )
    (net (code "134") (name "/UART4_TX") (class "Default")
      (node (ref "U2") (pin "F10") (pinfunction "PTC15_._UART4_TX_._FB_AD24_F10") (pintype "bidirectional"))
    )
    (net (code "135") (name "/ULPI_CLK") (class "Default")
      (node (ref "U2") (pin "R12") (pinfunction "PTA6_._ADC3_SE6a_._ULPI_CLK_._FTM0_CH3_._I2S1_RXD0_._CLKOUT_._TRACE__CLKOUT_R12") (pintype "bidirectional"))
    )
    (net (code "136") (name "/ULPI_DATA0") (class "Default")
      (node (ref "U2") (pin "P13") (pinfunction "PTA10_._ADC3_SE4a_._ULPI_DATA0_._FTM2_CH0_._MII0_RXD2_._FTM2_QD__PHA_._TRACE_D0_P13") (pintype "bidirectional"))
    )
    (net (code "137") (name "/ULPI_DATA1") (class "Default")
      (node (ref "U2") (pin "R13") (pinfunction "PTA11_._ADC3_SE15_._ULPI_DATA1_._FTM2_CH1_._MII0_RXCLK_._FTM2_QD__PHB_R13") (pintype "bidirectional"))
    )
    (net (code "138") (name "/ULPI_DATA2") (class "Default")
      (node (ref "U2") (pin "N13") (pinfunction "PTA24_._CMP3_IN4_._ULPI_DATA2_._MII0_TXD2_._FB_A29_N13") (pintype "bidirectional"))
    )
    (net (code "139") (name "/ULPI_DATA3") (class "Default")
      (node (ref "U2") (pin "R14") (pinfunction "PTA25_._CMP3_IN5_._ULPI_DATA3_._MII0_TXCLK_._FB_A28_R14") (pintype "bidirectional"))
    )
    (net (code "140") (name "/ULPI_DATA4") (class "Default")
      (node (ref "U2") (pin "M13") (pinfunction "PTA26_._ADC2_SE15_._ULPI_DATA4_._MII0_TXD3_._FB_A27_M13") (pintype "bidirectional"))
    )
    (net (code "141") (name "/ULPI_DATA5") (class "Default")
      (node (ref "U2") (pin "R15") (pinfunction "PTA27_._ADC2_SE14_._ULPI_DATA5_._MII0_CRS_._FB_A26_R15") (pintype "bidirectional"))
    )
    (net (code "142") (name "/ULPI_DATA6") (class "Default")
      (node (ref "U2") (pin "P14") (pinfunction "PTA28_._ADC2_SE13_._ULPI_DATA6_._MII0_TXER_._FB_A25_P14") (pintype "bidirectional"))
    )
    (net (code "143") (name "/ULPI_DATA7") (class "Default")
      (node (ref "U2") (pin "N14") (pinfunction "PTA29_._ADC2_SE12_._ULPI_DATA7_._MII0_COL_._FB_A24_N14") (pintype "bidirectional"))
    )
    (net (code "144") (name "/ULPI_DIR") (class "Default")
      (node (ref "U2") (pin "P12") (pinfunction "PTA7_._ADC0_SE10_._ULPI_DIR_._FTM0_CH4_._I2S1_RX_BCLK_._TRACE_D3_P12") (pintype "bidirectional"))
    )
    (net (code "145") (name "/ULPI_NXT") (class "Default")
      (node (ref "U2") (pin "N12") (pinfunction "PTA8_._ADC0_SE11_._ULPI_NXT_._FTM1_CH0_._I2S1_RX_FS_._FTM1_QD__PHA_._TRACE_D2_N12") (pintype "bidirectional"))
    )
    (net (code "146") (name "/ULPI_RESET") (class "Default")
      (node (ref "U2") (pin "T16") (pinfunction "PTA19_._XTAL0_._FTM1_FLT0_._FTM_CLKIN1_._LPTMR0_ALT1_T16") (pintype "bidirectional"))
    )
    (net (code "147") (name "/ULPI_STP") (class "Default")
      (node (ref "U2") (pin "T13") (pinfunction "PTA9_._ADC3_SE5a_._ULPI_STP_._FTM1_CH1_._MII0_RXD3_._FTM1_QD__PHB_._TRACE_D1_T13") (pintype "bidirectional"))
    )
    (net (code "148") (name "/USB1_N") (class "Default")
      (node (ref "U2") (pin "M2") (pinfunction "USB0_DM_M2") (pintype "bidirectional"))
    )
    (net (code "149") (name "/USB1_P") (class "Default")
      (node (ref "U2") (pin "M1") (pinfunction "USB0_DP_M1") (pintype "bidirectional"))
    )
    (net (code "150") (name "/USB_FLG") (class "Default")
      (node (ref "U2") (pin "K14") (pinfunction "PTB8_._UART3_RTS#_._FB_AD21_K14") (pintype "bidirectional"))
    )
    (net (code "151") (name "/USB_ID_OUT") (class "Default")
      (node (ref "U2") (pin "M15") (pinfunction "PTB5_._ADC1_SE11_._ENET0_1588__TMR3_._FTM2_FLT0_M15") (pintype "bidirectional"))
    )
    (net (code "152") (name "/USB_INT") (class "Default")
      (node (ref "U2") (pin "N15") (pinfunction "PTB4_._ADC1_SE10_._GLCD__CONTRAST_._ENET0_1588__TMR2_._FTM1_FLT0_N15") (pintype "bidirectional"))
    )
    (net (code "153") (name "/WIFI_INT") (class "Default")
      (node (ref "U2") (pin "L15") (pinfunction "PTB7_._ADC1_SE13_._FB_AD22_L15") (pintype "bidirectional"))
    )
    (net (code "154") (name "/WIFI_PWR_EN") (class "Default")
      (node (ref "U2") (pin "L5") (pinfunction "TAMPER1_L5") (pintype "bidirectional"))
    )
    (net (code "155") (name "/WIFI_PWR_ON") (class "Default")
      (node (ref "U2") (pin "R5") (pinfunction "TAMPER3_R5") (pintype "bidirectional"))
    )
    (net (code "156") (name "/XTAL") (class "Default")
      (node (ref "C4") (pin "1") (pinfunction "1_1") (pintype "passive"))
      (node (ref "R1") (pin "1") (pinfunction "1_1") (pintype "passive"))
      (node (ref "U2") (pin "R7") (pinfunction "PTE25_._ADC0_SE18_._XTAL1_._CAN1_RX_._UART4_RX_._I2S1_TX_BCLK_._GLCD_D14_._EWM_IN_._I2S1_TXD1_R7") (pintype "bidirectional"))
      (node (ref "Z2") (pin "1") (pinfunction "1_1") (pintype "passive"))
    )
    (net (code "157") (name "GND") (class "Default")
      (node (ref "C1") (pin "2") (pinfunction "2_2") (pintype "passive"))
      (node (ref "C2") (pin "2") (pinfunction "2_2") (pintype "passive"))
      (node (ref "C3") (pin "2") (pinfunction "2_2") (pintype "passive"))
      (node (ref "C4") (pin "2") (pinfunction "2_2") (pintype "passive"))
      (node (ref "C5") (pin "2") (pinfunction "2_2") (pintype "passive"))
      (node (ref "R7") (pin "2") (pinfunction "2_2") (pintype "passive"))
      (node (ref "X1") (pin "1") (pinfunction "GND_1") (pintype "power_in"))
      (node (ref "X1") (pin "10") (pinfunction "GND_10") (pintype "power_in"))
      (node (ref "X1") (pin "6") (pinfunction "RTCK_6") (pintype "input"))
      (node (ref "Z2") (pin "2") (pinfunction "2_2") (pintype "passive"))
      (node (ref "Z2") (pin "4") (pinfunction "4_4") (pintype "passive"))
    )
    (net (code "158") (name "Net-(U2A-EXTAL32)") (class "Default")
      (node (ref "C2") (pin "1") (pinfunction "1_1") (pintype "passive"))
      (node (ref "U2") (pin "T5") (pinfunction "EXTAL32_T5") (pintype "bidirectional"))
      (node (ref "Z1") (pin "2") (pinfunction "2_2") (pintype "passive"))
    )
    (net (code "159") (name "Net-(U2A-XTAL32)") (class "Default")
      (node (ref "C1") (pin "1") (pinfunction "1_1") (pintype "passive"))
      (node (ref "U2") (pin "T6") (pinfunction "XTAL32_T6") (pintype "bidirectional"))
      (node (ref "Z1") (pin "1") (pinfunction "1_1") (pintype "passive"))
    )
    (net (code "160") (name "Net-(X1-RESET)") (class "Default")
      (node (ref "D1") (pin "1") (pintype "passive"))
      (node (ref "X1") (pin "8") (pinfunction "RESET_8") (pintype "output"))
    )
    (net (code "161") (name "unconnected-(U2A-TAMPER2-PadL6)") (class "Default")
      (node (ref "U2") (pin "L6") (pinfunction "TAMPER2_L6") (pintype "bidirectional"))
    )
    (net (code "162") (name "unconnected-(X1-TRST-Pad2)") (class "Default")
      (node (ref "X1") (pin "2") (pinfunction "TRST_2") (pintype "passive"))
    )
  )
)
